# Sheet_2.net
KiCad netlist of a schematic drawn in Altium Designer
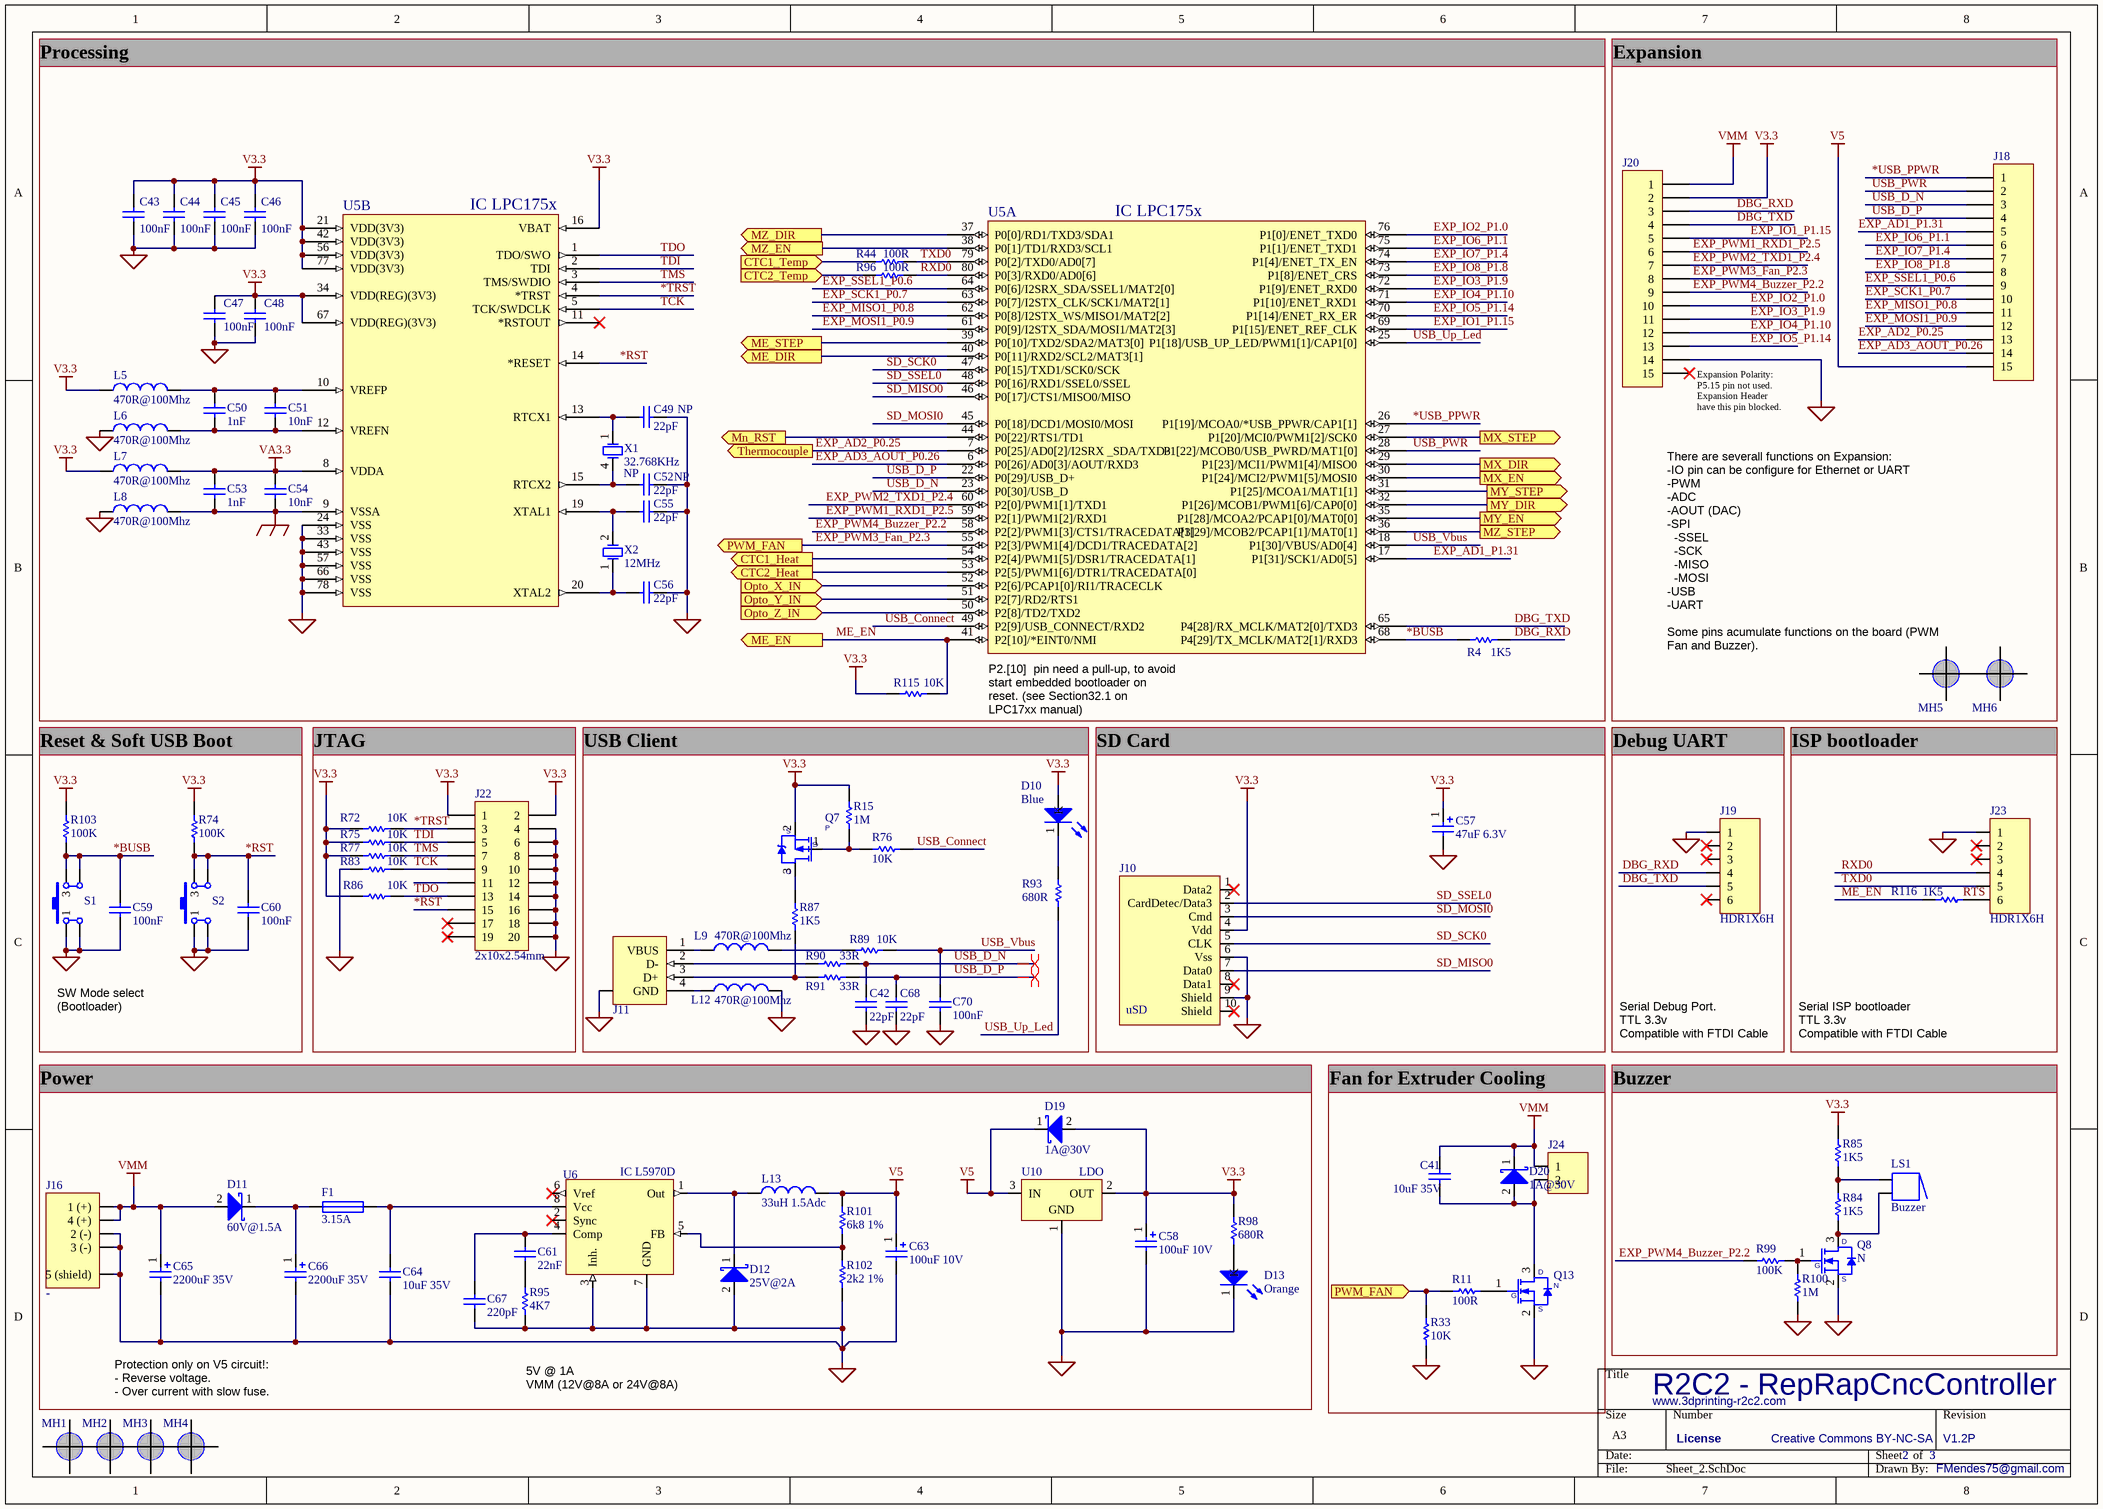
[diagram p0: Sheet_2.SchDoc]

(export (version "E")
  (design (tool "Eeschema 10.0.6"))
  (components
    (comp (ref "C41")
      (value "10uF 35V")
      (footprint "CAPC3216M")
      (description "Capacitor - MLCC; 10uF; 35V;")
      (fields (field (name "PART NUMBER") "10000002") (field (name "MANUFACTURER") "Taiyo Yuden"))
      (libsource (lib "HB_DB_Components") (part "Cap Non Pol"))
    )
    (comp (ref "C42")
      (value "22pF")
      (footprint "CAPC1608M")
      (description "Capacitor - MLCC; 0603; NP0; 50V")
      (fields (field (name "PART NUMBER") "10000056") (field (name "MANUFACTURER") "Multicomp"))
      (libsource (lib "HB_DB_Components") (part "Cap Non Pol"))
    )
    (comp (ref "C43")
      (value "100nF")
      (footprint "CAPC1608M")
      (description "Capacitor - MLCC; 0603; NP0; 50V")
      (fields (field (name "PART NUMBER") "10000054") (field (name "MANUFACTURER") "Multicomp"))
      (libsource (lib "HB_DB_Components") (part "Cap Non Pol"))
    )
    (comp (ref "C44")
      (value "100nF")
      (footprint "CAPC1608M")
      (description "Capacitor - MLCC; 0603; NP0; 50V")
      (fields (field (name "PART NUMBER") "10000054") (field (name "MANUFACTURER") "Multicomp"))
      (libsource (lib "HB_DB_Components") (part "Cap Non Pol"))
    )
    (comp (ref "C45")
      (value "100nF")
      (footprint "CAPC1608M")
      (description "Capacitor - MLCC; 0603; NP0; 50V")
      (fields (field (name "PART NUMBER") "10000054") (field (name "MANUFACTURER") "Multicomp"))
      (libsource (lib "HB_DB_Components") (part "Cap Non Pol"))
    )
    (comp (ref "C46")
      (value "100nF")
      (footprint "CAPC1608M")
      (description "Capacitor - MLCC; 0603; NP0; 50V")
      (fields (field (name "PART NUMBER") "10000054") (field (name "MANUFACTURER") "Multicomp"))
      (libsource (lib "HB_DB_Components") (part "Cap Non Pol"))
    )
    (comp (ref "C47")
      (value "100nF")
      (footprint "CAPC1608M")
      (description "Capacitor - MLCC; 0603; NP0; 50V")
      (fields (field (name "PART NUMBER") "10000054") (field (name "MANUFACTURER") "Multicomp"))
      (libsource (lib "HB_DB_Components") (part "Cap Non Pol"))
    )
    (comp (ref "C48")
      (value "100nF")
      (footprint "CAPC1608M")
      (description "Capacitor - MLCC; 0603; NP0; 50V")
      (fields (field (name "PART NUMBER") "10000054") (field (name "MANUFACTURER") "Multicomp"))
      (libsource (lib "HB_DB_Components") (part "Cap Non Pol"))
    )
    (comp (ref "C49")
      (value "22pF")
      (footprint "CAPC1608M")
      (description "Capacitor - MLCC; 0603; NP0; 50V")
      (fields
        (field (name "PART NUMBER") "10000056")
        (field (name "MANUFACTURER") "Multicomp")
        (field (name "POPULATE") "NP")
      )
      (libsource (lib "HB_DB_Components") (part "Cap Non Pol"))
    )
    (comp (ref "C50")
      (value "1nF")
      (footprint "CAPC1608M")
      (description "Capacitor - MLCC; 0603; NP0; 50V")
      (fields (field (name "PART NUMBER") "10000058") (field (name "MANUFACTURER") "Multicomp"))
      (libsource (lib "HB_DB_Components") (part "Cap Non Pol"))
    )
    (comp (ref "C51")
      (value "10nF")
      (footprint "CAPC1608M")
      (description "Capacitor - MLCC; 0603; NP0; 50V")
      (fields (field (name "PART NUMBER") "10000057") (field (name "MANUFACTURER") "Multicomp"))
      (libsource (lib "HB_DB_Components") (part "Cap Non Pol"))
    )
    (comp (ref "C52")
      (value "22pF")
      (footprint "CAPC1608M")
      (description "Capacitor - MLCC; 0603; NP0; 50V")
      (fields
        (field (name "PART NUMBER") "10000056")
        (field (name "MANUFACTURER") "Multicomp")
        (field (name "POPULATE") "NP")
      )
      (libsource (lib "HB_DB_Components") (part "Cap Non Pol"))
    )
    (comp (ref "C53")
      (value "1nF")
      (footprint "CAPC1608M")
      (description "Capacitor - MLCC; 0603; NP0; 50V")
      (fields (field (name "PART NUMBER") "10000058") (field (name "MANUFACTURER") "Multicomp"))
      (libsource (lib "HB_DB_Components") (part "Cap Non Pol"))
    )
    (comp (ref "C54")
      (value "10nF")
      (footprint "CAPC1608M")
      (description "Capacitor - MLCC; 0603; NP0; 50V")
      (fields (field (name "PART NUMBER") "10000057") (field (name "MANUFACTURER") "Multicomp"))
      (libsource (lib "HB_DB_Components") (part "Cap Non Pol"))
    )
    (comp (ref "C55")
      (value "22pF")
      (footprint "CAPC1608M")
      (description "Capacitor - MLCC; 0603; NP0; 50V")
      (fields (field (name "PART NUMBER") "10000056") (field (name "MANUFACTURER") "Multicomp"))
      (libsource (lib "HB_DB_Components") (part "Cap Non Pol"))
    )
    (comp (ref "C56")
      (value "22pF")
      (footprint "CAPC1608M")
      (description "Capacitor - MLCC; 0603; NP0; 50V")
      (fields (field (name "PART NUMBER") "10000056") (field (name "MANUFACTURER") "Multicomp"))
      (libsource (lib "HB_DB_Components") (part "Cap Non Pol"))
    )
    (comp (ref "C57")
      (value "47uF 6.3V")
      (footprint "CAPCP3825M")
      (description "Capacitor - MLCC Y5V; 47UF; 6.3V")
      (fields (field (name "PART NUMBER") "10000005") (field (name "MANUFACTURER") "MULTICOMP"))
      (libsource (lib "HB_DB_Components") (part "Cap Pol"))
    )
    (comp (ref "C58")
      (value "100uF 10V")
      (footprint "CAPAE6666X54M")
      (description "Capacitor - Al. Electrolytic; 100uF, 16V")
      (fields (field (name "PART NUMBER") "10000086") (field (name "MANUFACTURER") "Nichicon"))
      (libsource (lib "HB_DB_Components") (part "Cap Pol"))
    )
    (comp (ref "C59")
      (value "100nF")
      (footprint "CAPC1608M")
      (description "Capacitor - MLCC; 0603; NP0; 50V")
      (fields (field (name "PART NUMBER") "10000054") (field (name "MANUFACTURER") "Multicomp"))
      (libsource (lib "HB_DB_Components") (part "Cap Non Pol"))
    )
    (comp (ref "C60")
      (value "100nF")
      (footprint "CAPC1608M")
      (description "Capacitor - MLCC; 0603; NP0; 50V")
      (fields (field (name "PART NUMBER") "10000054") (field (name "MANUFACTURER") "Multicomp"))
      (libsource (lib "HB_DB_Components") (part "Cap Non Pol"))
    )
    (comp (ref "C61")
      (value "22nF")
      (footprint "CAPC1608M")
      (description "Capacitor - MLCC; 0603; NP0; 50V")
      (fields (field (name "PART NUMBER") "10000066") (field (name "MANUFACTURER") "Multicomp"))
      (libsource (lib "HB_DB_Components") (part "Cap Non Pol"))
    )
    (comp (ref "C63")
      (value "100uF 10V")
      (footprint "CAPAE6666X54M")
      (description "Capacitor - Al. Electrolytic; 100uF, 16V")
      (fields (field (name "PART NUMBER") "10000086") (field (name "MANUFACTURER") "Nichicon"))
      (libsource (lib "HB_DB_Components") (part "Cap Pol"))
    )
    (comp (ref "C64")
      (value "10uF 35V")
      (footprint "CAPC3216M")
      (description "Capacitor - MLCC; 10uF; 35V;")
      (fields (field (name "PART NUMBER") "10000002") (field (name "MANUFACTURER") "Taiyo Yuden"))
      (libsource (lib "HB_DB_Components") (part "Cap Non Pol"))
    )
    (comp (ref "C65")
      (value "2200uF 35V")
      (footprint "CAPPR7.5-16x25")
      (description "Capacitor - Al. Electrolytic; 2200uF; 35V")
      (fields (field (name "PART NUMBER") "10000006") (field (name "MANUFACTURER") "PANASONIC"))
      (libsource (lib "HB_DB_Components") (part "Cap Pol"))
    )
    (comp (ref "C66")
      (value "2200uF 35V")
      (footprint "CAPPR7.5-16x25")
      (description "Capacitor - Al. Electrolytic; 2200uF; 35V")
      (fields (field (name "PART NUMBER") "10000006") (field (name "MANUFACTURER") "PANASONIC"))
      (libsource (lib "HB_DB_Components") (part "Cap Pol"))
    )
    (comp (ref "C67")
      (value "220pF")
      (footprint "CAPC1608M")
      (description "Capacitor - MLCC; 0603; NP0; 50V")
      (fields (field (name "PART NUMBER") "10000055") (field (name "MANUFACTURER") "Multicomp"))
      (libsource (lib "HB_DB_Components") (part "Cap Non Pol"))
    )
    (comp (ref "C68")
      (value "22pF")
      (footprint "CAPC1608M")
      (description "Capacitor - MLCC; 0603; NP0; 50V")
      (fields (field (name "PART NUMBER") "10000056") (field (name "MANUFACTURER") "Multicomp"))
      (libsource (lib "HB_DB_Components") (part "Cap Non Pol"))
    )
    (comp (ref "C70")
      (value "100nF")
      (footprint "CAPC1608M")
      (description "Capacitor - MLCC; 0603; NP0; 50V")
      (fields (field (name "PART NUMBER") "10000054") (field (name "MANUFACTURER") "Multicomp"))
      (libsource (lib "HB_DB_Components") (part "Cap Non Pol"))
    )
    (comp (ref "D10")
      (value "Blue")
      (footprint "LEDM_3216X12M")
      (description "Led - 1206; Blue OSRAM")
      (fields (field (name "PART NUMBER") "10000065") (field (name "MANUFACTURER") "OSRAM"))
      (libsource (lib "HB_DB_Components") (part "LED"))
    )
    (comp (ref "D11")
      (value "60V@1.5A")
      (footprint "SMA")
      (description "Diode - Schottky; 1.5A; 60V")
      (fields (field (name "PART NUMBER") "10000010") (field (name "MANUFACTURER") "VISHAY"))
      (libsource (lib "HB_DB_Components") (part "D Schottky"))
    )
    (comp (ref "D12")
      (value "25V@2A")
      (footprint "SMB")
      (description "Diode - Schottky; 25V; 2A")
      (fields (field (name "PART NUMBER") "10000009") (field (name "MANUFACTURER") "ST"))
      (libsource (lib "HB_DB_Components") (part "D Schottky"))
    )
    (comp (ref "D13")
      (value "Orange")
      (footprint "LEDM_3216X12M")
      (description "Led - 1206; Orange OSRAM")
      (fields (field (name "PART NUMBER") "10000007") (field (name "MANUFACTURER") "OSRAM"))
      (libsource (lib "HB_DB_Components") (part "LED"))
    )
    (comp (ref "D19")
      (value "1A@30V")
      (footprint "SOD323")
      (description "Diode - Schottky; 30V; 1A;")
      (fields (field (name "PART NUMBER") "10000085") (field (name "MANUFACTURER") "NXP"))
      (libsource (lib "HB_DB_Components") (part "D Schottky"))
    )
    (comp (ref "D20")
      (value "1A@30V")
      (footprint "SOD323")
      (description "Diode - Schottky; 30V; 1A;")
      (fields (field (name "PART NUMBER") "10000085") (field (name "MANUFACTURER") "NXP"))
      (libsource (lib "HB_DB_Components") (part "D Schottky"))
    )
    (comp (ref "F1")
      (value "3.15A")
      (footprint "RESC1608M")
      (description "Fuse - 0603; Itrip=3.15A")
      (fields (field (name "PART NUMBER") "10000011") (field (name "MANUFACTURER") "Bourns"))
      (libsource (lib "HB_DB_Components") (part "F"))
    )
    (comp (ref "J10")
      (value "uSD")
      (footprint "3M_2900")
      (description "Connector - MicroSD Card 8pin; PCB; Gold")
      (fields (field (name "PART NUMBER") "10000029") (field (name "MANUFACTURER") "Amphenol"))
      (libsource (lib "HB_DB_Components") (part "Con uSD"))
    )
    (comp (ref "J11") (value "Con 4 USB") (libsource (lib "HB") (part "Con 4 USB")))
    (comp (ref "J16")
      (value "-")
      (footprint "KYCON_KPJX-4S")
      (description "Connector - PCB; Female Receptacle; 4 way; Hor.")
      (fields (field (name "PART NUMBER") "10000099") (field (name "MANUFACTURER") "Kycon"))
      (libsource (lib "HB_DB_Components") (part "Con 5 KPJX-4S"))
    )
    (comp (ref "J18")
      (value "Con 15")
      (footprint "HDR1X15")
      (description "Connector - Header 15x1")
      (fields (field (name "PART NUMBER") "10000067"))
      (libsource (lib "HB_DB_Components") (part "Con 15"))
    )
    (comp (ref "J19")
      (value "HDR1X6H")
      (footprint "HDR1X6H")
      (description "Connector - Header 1x6; Hor.")
      (fields (field (name "PART NUMBER") "10000074"))
      (libsource (lib "HB_DB_Components") (part "Con 6"))
    )
    (comp (ref "J20")
      (value "Con 15")
      (footprint "HDR1X15")
      (description "Connector - Header 15x1")
      (fields (field (name "PART NUMBER") "10000067"))
      (libsource (lib "") (part "Con 15_1"))
    )
    (comp (ref "J22")
      (value "2x10x2.54mm")
      (footprint "HDR2X10")
      (description "Connector - PCB; Male Receptacle; 2.54mm; 2way; Vert.")
      (fields (field (name "PART NUMBER") "10000064") (field (name "MANUFACTURER") "SAMTEC"))
      (libsource (lib "HB_DB_Components") (part "Con 10X2"))
    )
    (comp (ref "J23")
      (value "HDR1X6H")
      (footprint "HDR1X6H")
      (description "Connector - Header 1x6; Hor.")
      (fields (field (name "PART NUMBER") "10000074"))
      (libsource (lib "HB_DB_Components") (part "Con 6"))
    )
    (comp (ref "J24")
      (value "Con 2")
      (footprint "MOLEX_22-29-2021")
      (description "Connector - PCB; Header; SQ Pin, 2 way; 2.54mm; Vert")
      (fields (field (name "PART NUMBER") "10000097") (field (name "MANUFACTURER") "Molex"))
      (libsource (lib "HB_DB_Components") (part "Con 2"))
    )
    (comp (ref "L5")
      (value "470R@100Mhz")
      (footprint "INDC1608M")
      (description "Ferrite Bead - 470OHM; 0603")
      (fields (field (name "PART NUMBER") "10000032") (field (name "MANUFACTURER") "MURATA"))
      (libsource (lib "HB_DB_Components") (part "Ind"))
    )
    (comp (ref "L6")
      (value "470R@100Mhz")
      (footprint "INDC1608M")
      (description "Ferrite Bead - 470OHM; 0603")
      (fields (field (name "PART NUMBER") "10000032") (field (name "MANUFACTURER") "MURATA"))
      (libsource (lib "HB_DB_Components") (part "Ind"))
    )
    (comp (ref "L7")
      (value "470R@100Mhz")
      (footprint "INDC1608M")
      (description "Ferrite Bead - 470OHM; 0603")
      (fields (field (name "PART NUMBER") "10000032") (field (name "MANUFACTURER") "MURATA"))
      (libsource (lib "HB_DB_Components") (part "Ind"))
    )
    (comp (ref "L8")
      (value "470R@100Mhz")
      (footprint "INDC1608M")
      (description "Ferrite Bead - 470OHM; 0603")
      (fields (field (name "PART NUMBER") "10000032") (field (name "MANUFACTURER") "MURATA"))
      (libsource (lib "HB_DB_Components") (part "Ind"))
    )
    (comp (ref "L9")
      (value "470R@100Mhz")
      (footprint "INDC1608M")
      (description "Ferrite Bead - 470OHM; 0603")
      (fields (field (name "PART NUMBER") "10000032") (field (name "MANUFACTURER") "MURATA"))
      (libsource (lib "HB_DB_Components") (part "Ind"))
    )
    (comp (ref "L12")
      (value "470R@100Mhz")
      (footprint "INDC1608M")
      (description "Ferrite Bead - 470OHM; 0603")
      (fields (field (name "PART NUMBER") "10000032") (field (name "MANUFACTURER") "MURATA"))
      (libsource (lib "HB_DB_Components") (part "Ind"))
    )
    (comp (ref "L13")
      (value "33uH 1.5Adc")
      (footprint "INDP9898X58M")
      (description "Inductor - 33uH; Isat=2.9A; In=1.5A")
      (fields (field (name "PART NUMBER") "10000081") (field (name "MANUFACTURER") "Bourns"))
      (libsource (lib "HB_DB_Components") (part "Ind"))
    )
    (comp (ref "LS1")
      (value "Buzzer")
      (footprint "TDK_PS17")
      (description "Buzzer - Piezo; 70dB; Diam.17mm")
      (fields (field (name "PART NUMBER") "10000068") (field (name "MANUFACTURER") "TDK"))
      (libsource (lib "HB_DB_Components") (part "Buzzer"))
    )
    (comp (ref "MH1")
      (value "MH")
      (footprint "MH_M3")
      (description "PCB Symbol - Mounting Hole M3")
      (fields (field (name "PART NUMBER") "1000000"))
      (libsource (lib "HB_DB_Components") (part "MH"))
    )
    (comp (ref "MH2")
      (value "MH")
      (footprint "MH_M3")
      (description "PCB Symbol - Mounting Hole M3")
      (fields (field (name "PART NUMBER") "1000000"))
      (libsource (lib "HB_DB_Components") (part "MH"))
    )
    (comp (ref "MH3")
      (value "MH")
      (footprint "MH_M3")
      (description "PCB Symbol - Mounting Hole M3")
      (fields (field (name "PART NUMBER") "1000000"))
      (libsource (lib "HB_DB_Components") (part "MH"))
    )
    (comp (ref "MH4")
      (value "MH")
      (footprint "MH_M3")
      (description "PCB Symbol - Mounting Hole M3")
      (fields (field (name "PART NUMBER") "1000000"))
      (libsource (lib "HB_DB_Components") (part "MH"))
    )
    (comp (ref "MH5")
      (value "MH")
      (footprint "MH_M3_2")
      (description "PCB Symbol - Mounting Hole M3")
      (fields (field (name "PART NUMBER") "100001"))
      (libsource (lib "HB_DB_Components") (part "MH"))
    )
    (comp (ref "MH6")
      (value "MH")
      (footprint "MH_M3_2")
      (description "PCB Symbol - Mounting Hole M3")
      (fields (field (name "PART NUMBER") "100001"))
      (libsource (lib "HB_DB_Components") (part "MH"))
    )
    (comp (ref "Q7")
      (value "P")
      (footprint "SOT23-3M")
      (description "Mosfet - Power; Vdss=-30v; Rds=0.60; Id=-0.6A")
      (fields (field (name "PART NUMBER") "10000076") (field (name "MANUFACTURER") "IR"))
      (libsource (lib "HB_DB_Components") (part "MOS-P"))
    )
    (comp (ref "Q8")
      (value "N")
      (footprint "SOT323-3AM")
      (description "Mosfet - N; 60V; 0.3A;")
      (fields (field (name "PART NUMBER") "10000039") (field (name "MANUFACTURER") "NXP"))
      (libsource (lib "HB_DB_Components") (part "Q MOSFET-N"))
    )
    (comp (ref "Q13")
      (value "N")
      (footprint "SOT323-3AM")
      (description "Mosfet - N; 60V; 0.3A;")
      (fields (field (name "PART NUMBER") "10000039") (field (name "MANUFACTURER") "NXP"))
      (libsource (lib "HB_DB_Components") (part "Q MOSFET-N"))
    )
    (comp (ref "R4")
      (value "1K5")
      (footprint "RESC1608M")
      (description "Resistor")
      (fields (field (name "PART NUMBER") "10000048") (field (name "MANUFACTURER") "Multicomp"))
      (libsource (lib "HB_DB_Components") (part "Res"))
    )
    (comp (ref "R11")
      (value "100R")
      (footprint "RESC1608M")
      (description "Resistor - 0603; 0.063W; 1%")
      (fields (field (name "PART NUMBER") "10000042") (field (name "MANUFACTURER") "Multicomp"))
      (libsource (lib "HB_DB_Components") (part "Res"))
    )
    (comp (ref "R15")
      (value "1M")
      (footprint "RESC1608M")
      (description "Resistor - 0603; 0.063W; 1%")
      (fields (field (name "PART NUMBER") "10000049") (field (name "MANUFACTURER") "Multicomp"))
      (libsource (lib "HB_DB_Components") (part "Res"))
    )
    (comp (ref "R33")
      (value "10K")
      (footprint "RESC1608M")
      (description "Resistor - 0603; 0.063W; 1%")
      (fields (field (name "PART NUMBER") "10000044") (field (name "MANUFACTURER") "Multicomp"))
      (libsource (lib "HB_DB_Components") (part "Res"))
    )
    (comp (ref "R44")
      (value "100R")
      (footprint "RESC1608M")
      (description "Resistor - 0603; 0.063W; 1%")
      (fields (field (name "PART NUMBER") "10000042") (field (name "MANUFACTURER") "Multicomp"))
      (libsource (lib "HB_DB_Components") (part "Res"))
    )
    (comp (ref "R72")
      (value "10K")
      (footprint "RESC1608M")
      (description "Resistor - 0603; 0.063W; 1%")
      (fields (field (name "PART NUMBER") "10000044") (field (name "MANUFACTURER") "Multicomp"))
      (libsource (lib "HB_DB_Components") (part "Res"))
    )
    (comp (ref "R74")
      (value "100K")
      (footprint "RESC1608M")
      (description "Resistor - 0603; 0.063W; 1%")
      (fields (field (name "PART NUMBER") "10000045") (field (name "MANUFACTURER") "Multicomp"))
      (libsource (lib "HB_DB_Components") (part "Res"))
    )
    (comp (ref "R75")
      (value "10K")
      (footprint "RESC1608M")
      (description "Resistor - 0603; 0.063W; 1%")
      (fields (field (name "PART NUMBER") "10000044") (field (name "MANUFACTURER") "Multicomp"))
      (libsource (lib "HB_DB_Components") (part "Res"))
    )
    (comp (ref "R76")
      (value "10K")
      (footprint "RESC1608M")
      (description "Resistor - 0603; 0.063W; 1%")
      (fields (field (name "PART NUMBER") "10000044") (field (name "MANUFACTURER") "Multicomp"))
      (libsource (lib "HB_DB_Components") (part "Res"))
    )
    (comp (ref "R77")
      (value "10K")
      (footprint "RESC1608M")
      (description "Resistor - 0603; 0.063W; 1%")
      (fields (field (name "PART NUMBER") "10000044") (field (name "MANUFACTURER") "Multicomp"))
      (libsource (lib "HB_DB_Components") (part "Res"))
    )
    (comp (ref "R83")
      (value "10K")
      (footprint "RESC1608M")
      (description "Resistor - 0603; 0.063W; 1%")
      (fields (field (name "PART NUMBER") "10000044") (field (name "MANUFACTURER") "Multicomp"))
      (libsource (lib "HB_DB_Components") (part "Res"))
    )
    (comp (ref "R84")
      (value "1K5")
      (footprint "RESC1608M")
      (description "Resistor - 0603; 0.063W; 1%")
      (fields (field (name "PART NUMBER") "10000048") (field (name "MANUFACTURER") "Multicomp"))
      (libsource (lib "HB_DB_Components") (part "Res"))
    )
    (comp (ref "R85")
      (value "1K5")
      (footprint "RESC1608M")
      (description "Resistor - 0603; 0.063W; 1%")
      (fields (field (name "PART NUMBER") "10000048") (field (name "MANUFACTURER") "Multicomp"))
      (libsource (lib "HB_DB_Components") (part "Res"))
    )
    (comp (ref "R86")
      (value "10K")
      (footprint "RESC1608M")
      (description "Resistor - 0603; 0.063W; 1%")
      (fields (field (name "PART NUMBER") "10000044") (field (name "MANUFACTURER") "Multicomp"))
      (libsource (lib "HB_DB_Components") (part "Res"))
    )
    (comp (ref "R87")
      (value "1K5")
      (footprint "RESC1608M")
      (description "Resistor - 0603; 0.063W; 1%")
      (fields (field (name "PART NUMBER") "10000048") (field (name "MANUFACTURER") "Multicomp"))
      (libsource (lib "HB_DB_Components") (part "Res"))
    )
    (comp (ref "R89")
      (value "10K")
      (footprint "RESC1608M")
      (description "Resistor - 0603; 0.063W; 1%")
      (fields (field (name "PART NUMBER") "10000044") (field (name "MANUFACTURER") "Multicomp"))
      (libsource (lib "HB_DB_Components") (part "Res"))
    )
    (comp (ref "R90")
      (value "33R")
      (footprint "RESC1608M")
      (description "Resistor - 0603; 0.063W; 1%")
      (fields (field (name "PART NUMBER") "10000053") (field (name "MANUFACTURER") "Multicomp"))
      (libsource (lib "HB_DB_Components") (part "Res"))
    )
    (comp (ref "R91")
      (value "33R")
      (footprint "RESC1608M")
      (description "Resistor - 0603; 0.063W; 1%")
      (fields (field (name "PART NUMBER") "10000053") (field (name "MANUFACTURER") "Multicomp"))
      (libsource (lib "HB_DB_Components") (part "Res"))
    )
    (comp (ref "R93")
      (value "680R")
      (footprint "RESC1608M")
      (description "Resistor - 0603; 0.063W; 1%")
      (fields (field (name "PART NUMBER") "10000061") (field (name "MANUFACTURER") "Multicomp"))
      (libsource (lib "HB_DB_Components") (part "Res"))
    )
    (comp (ref "R95")
      (value "4K7")
      (footprint "RESC1608M")
      (description "Resistor - 0603; 0.063W; 1%")
      (fields (field (name "PART NUMBER") "10000050") (field (name "MANUFACTURER") "Multicomp"))
      (libsource (lib "HB_DB_Components") (part "Res"))
    )
    (comp (ref "R96")
      (value "100R")
      (footprint "RESC1608M")
      (description "Resistor - 0603; 0.063W; 1%")
      (fields (field (name "PART NUMBER") "10000042") (field (name "MANUFACTURER") "Multicomp"))
      (libsource (lib "HB_DB_Components") (part "Res"))
    )
    (comp (ref "R98")
      (value "680R")
      (footprint "RESC1608M")
      (description "Resistor - 0603; 0.063W; 1%")
      (fields (field (name "PART NUMBER") "10000061") (field (name "MANUFACTURER") "Multicomp"))
      (libsource (lib "HB_DB_Components") (part "Res"))
    )
    (comp (ref "R99")
      (value "100K")
      (footprint "RESC1608M")
      (description "Resistor - 0603; 0.063W; 1%")
      (fields (field (name "PART NUMBER") "10000045") (field (name "MANUFACTURER") "Multicomp"))
      (libsource (lib "HB_DB_Components") (part "Res"))
    )
    (comp (ref "R100")
      (value "1M")
      (footprint "RESC1608M")
      (description "Resistor - 0603; 0.063W; 1%")
      (fields (field (name "PART NUMBER") "10000049") (field (name "MANUFACTURER") "Multicomp"))
      (libsource (lib "HB_DB_Components") (part "Res"))
    )
    (comp (ref "R101")
      (value "6k8 1%")
      (footprint "RESC1608M")
      (description "Resistor - 0603; 0.063W; 1%")
      (fields (field (name "PART NUMBER") "10000080") (field (name "MANUFACTURER") "Vishay"))
      (libsource (lib "HB_DB_Components") (part "Res"))
    )
    (comp (ref "R102")
      (value "2k2 1%")
      (footprint "RESC1608M")
      (description "Resistor - 0603; 0.063W; 1%")
      (fields (field (name "PART NUMBER") "10000079") (field (name "MANUFACTURER") "Vishay"))
      (libsource (lib "HB_DB_Components") (part "Res"))
    )
    (comp (ref "R103")
      (value "100K")
      (footprint "RESC1608M")
      (description "Resistor - 0603; 0.063W; 1%")
      (fields (field (name "PART NUMBER") "10000045") (field (name "MANUFACTURER") "Multicomp"))
      (libsource (lib "HB_DB_Components") (part "Res"))
    )
    (comp (ref "R115")
      (value "10K")
      (footprint "RESC1608M")
      (description "Resistor - 0603; 0.063W; 1%")
      (fields (field (name "PART NUMBER") "10000044") (field (name "MANUFACTURER") "Multicomp"))
      (libsource (lib "HB_DB_Components") (part "Res"))
    )
    (comp (ref "R116")
      (value "1K5")
      (footprint "RESC1608M")
      (description "Resistor - 0603; 0.063W; 1%")
      (fields (field (name "PART NUMBER") "10000048") (field (name "MANUFACTURER") "Multicomp"))
      (libsource (lib "HB_DB_Components") (part "Res"))
    )
    (comp (ref "S1")
      (value "SW-PB")
      (footprint "SW_FSM6JSMA")
      (description "Switch - Micro; Tactile; SPNO")
      (fields (field (name "PART NUMBER") "10000019") (field (name "MANUFACTURER") "TYCO"))
      (libsource (lib "HB_DB_Components") (part "SW-PB"))
    )
    (comp (ref "S2")
      (value "SW-PB")
      (footprint "SW_FSM6JSMA")
      (description "Switch - Micro; Tactile; SPNO")
      (fields (field (name "PART NUMBER") "10000019") (field (name "MANUFACTURER") "TYCO"))
      (libsource (lib "HB_DB_Components") (part "SW-PB"))
    )
    (comp (ref "U5")
      (value "IC LPC175x")
      (footprint "TSQFP50P1400X1400X160-80M")
      (description "IC - uController ARM Cortex-M3, 100MHz")
      (fields (field (name "PART NUMBER") "10000013") (field (name "MANUFACTURER") "NXP"))
      (libsource (lib "HB_DB_Components") (part "IC LPC175x"))
    )
    (comp (ref "U6")
      (value "IC L5970D")
      (footprint "SOIC127P600-8M")
      (description "IC - DC-DC Reg.")
      (fields (field (name "PART NUMBER") "10000017") (field (name "MANUFACTURER") "ST"))
      (libsource (lib "HB_DB_Components") (part "IC L5970D"))
    )
    (comp (ref "U10")
      (value "LDO")
      (footprint "SOT223-4M")
      (description "IC - Fixed LDO Voltage Reg 3.3V 800mA")
      (fields (field (name "PART NUMBER") "10000082") (field (name "MANUFACTURER") "TI"))
      (libsource (lib "HB_DB_Components") (part "IC_TLV1117-3.3"))
    )
    (comp (ref "X1")
      (value "32.768KHz")
      (footprint "XTAL_800P380X250-4M")
      (description "Crystal - 32.768 kHz Low Profile; PLastic")
      (fields
        (field (name "PART NUMBER") "10000063")
        (field (name "MANUFACTURER") "ABRACON")
        (field (name "POPULATE") "NP")
      )
      (libsource (lib "HB_DB_Components") (part "XTAL_4"))
    )
    (comp (ref "X2")
      (value "12MHz")
      (footprint "HC49/4H_SMX")
      (description "Crystal - 12.0MHz")
      (fields (field (name "PART NUMBER") "10000040"))
      (libsource (lib "HB_DB_Components") (part "XTAL"))
    )
  )
  (nets
    (net (code "1") (name "/*BUSB") (class "Default")
      (node (ref "C59") (pin "2") (pinfunction "2_2") (pintype "passive"))
      (node (ref "R103") (pin "1") (pinfunction "1_1") (pintype "passive"))
      (node (ref "R4") (pin "1") (pinfunction "1_1") (pintype "passive"))
      (node (ref "S1") (pin "3") (pinfunction "3_3") (pintype "passive"))
      (node (ref "S1") (pin "4") (pinfunction "4_4") (pintype "passive"))
      (node (ref "U5") (pin "68") (pinfunction "P4[29]/TX_MCLK/MAT2[1]/RXD3_68") (pintype "bidirectional"))
    )
    (net (code "2") (name "/*RST") (class "Default")
      (node (ref "C60") (pin "2") (pinfunction "2_2") (pintype "passive"))
      (node (ref "J22") (pin "15") (pinfunction "15_15") (pintype "passive"))
      (node (ref "R74") (pin "1") (pinfunction "1_1") (pintype "passive"))
      (node (ref "S2") (pin "3") (pinfunction "3_3") (pintype "passive"))
      (node (ref "S2") (pin "4") (pinfunction "4_4") (pintype "passive"))
      (node (ref "U5") (pin "14") (pinfunction "*RESET_14") (pintype "input"))
    )
    (net (code "3") (name "/*TRST") (class "Default")
      (node (ref "J22") (pin "3") (pinfunction "3_3") (pintype "passive"))
      (node (ref "R72") (pin "2") (pinfunction "2_2") (pintype "passive"))
      (node (ref "U5") (pin "4") (pinfunction "*TRST_4") (pintype "input"))
    )
    (net (code "4") (name "/*USB_PPWR") (class "Default")
      (node (ref "J18") (pin "1") (pinfunction "1_1") (pintype "passive"))
      (node (ref "U5") (pin "26") (pinfunction "P1[19]/MCOA0/*USB_PPWR/CAP1[1]_26") (pintype "bidirectional"))
    )
    (net (code "5") (name "/CTC1_Heat") (class "Default")
      (node (ref "U5") (pin "54") (pinfunction "P2[4]/PWM1[5]/DSR1/TRACEDATA[1]_54") (pintype "bidirectional"))
    )
    (net (code "6") (name "/CTC1_Temp") (class "Default")
      (node (ref "R44") (pin "1") (pinfunction "1_1") (pintype "passive"))
    )
    (net (code "7") (name "/CTC2_Heat") (class "Default")
      (node (ref "U5") (pin "53") (pinfunction "P2[5]/PWM1[6]/DTR1/TRACEDATA[0]_53") (pintype "bidirectional"))
    )
    (net (code "8") (name "/CTC2_Temp") (class "Default")
      (node (ref "R96") (pin "1") (pinfunction "1_1") (pintype "passive"))
    )
    (net (code "9") (name "/DBG_RXD") (class "Default")
      (node (ref "J19") (pin "4") (pinfunction "4_4") (pintype "passive"))
      (node (ref "J20") (pin "3") (pinfunction "3_3") (pintype "passive"))
      (node (ref "R4") (pin "2") (pinfunction "2_2") (pintype "passive"))
    )
    (net (code "10") (name "/DBG_TXD") (class "Default")
      (node (ref "J19") (pin "5") (pinfunction "5_5") (pintype "passive"))
      (node (ref "J20") (pin "4") (pinfunction "4_4") (pintype "passive"))
      (node (ref "U5") (pin "65") (pinfunction "P4[28]/RX_MCLK/MAT2[0]/TXD3_65") (pintype "bidirectional"))
    )
    (net (code "11") (name "/EXP_AD1_P1.31") (class "Default")
      (node (ref "J18") (pin "5") (pinfunction "5_5") (pintype "passive"))
      (node (ref "U5") (pin "17") (pinfunction "P1[31]/SCK1/AD0[5]_17") (pintype "bidirectional"))
    )
    (net (code "12") (name "/EXP_AD2_P0.25") (class "Default")
      (node (ref "J18") (pin "13") (pinfunction "13_13") (pintype "passive"))
      (node (ref "U5") (pin "7") (pinfunction "P0[25]/AD0[2]/I2SRX__SDA/TXD3_7") (pintype "bidirectional"))
    )
    (net (code "13") (name "/EXP_AD3_AOUT_P0.26") (class "Default")
      (node (ref "J18") (pin "14") (pinfunction "14_14") (pintype "passive"))
      (node (ref "U5") (pin "6") (pinfunction "P0[26]/AD0[3]/AOUT/RXD3_6") (pintype "bidirectional"))
    )
    (net (code "14") (name "/EXP_IO1_P1.15") (class "Default")
      (node (ref "J20") (pin "5") (pinfunction "5_5") (pintype "passive"))
      (node (ref "U5") (pin "69") (pinfunction "P1[15]/ENET_REF_CLK_69") (pintype "bidirectional"))
    )
    (net (code "15") (name "/EXP_IO2_P1.0") (class "Default")
      (node (ref "J20") (pin "10") (pinfunction "10_10") (pintype "passive"))
      (node (ref "U5") (pin "76") (pinfunction "P1[0]/ENET_TXD0_76") (pintype "bidirectional"))
    )
    (net (code "16") (name "/EXP_IO3_P1.9") (class "Default")
      (node (ref "J20") (pin "11") (pinfunction "11_11") (pintype "passive"))
      (node (ref "U5") (pin "72") (pinfunction "P1[9]/ENET_RXD0_72") (pintype "bidirectional"))
    )
    (net (code "17") (name "/EXP_IO4_P1.10") (class "Default")
      (node (ref "J20") (pin "12") (pinfunction "12_12") (pintype "passive"))
      (node (ref "U5") (pin "71") (pinfunction "P1[10]/ENET_RXD1_71") (pintype "bidirectional"))
    )
    (net (code "18") (name "/EXP_IO5_P1.14") (class "Default")
      (node (ref "J20") (pin "13") (pinfunction "13_13") (pintype "passive"))
      (node (ref "U5") (pin "70") (pinfunction "P1[14]/ENET_RX_ER_70") (pintype "bidirectional"))
    )
    (net (code "19") (name "/EXP_IO6_P1.1") (class "Default")
      (node (ref "J18") (pin "6") (pinfunction "6_6") (pintype "passive"))
      (node (ref "U5") (pin "75") (pinfunction "P1[1]/ENET_TXD1_75") (pintype "bidirectional"))
    )
    (net (code "20") (name "/EXP_IO7_P1.4") (class "Default")
      (node (ref "J18") (pin "7") (pinfunction "7_7") (pintype "passive"))
      (node (ref "U5") (pin "74") (pinfunction "P1[4]/ENET_TX_EN_74") (pintype "bidirectional"))
    )
    (net (code "21") (name "/EXP_IO8_P1.8") (class "Default")
      (node (ref "J18") (pin "8") (pinfunction "8_8") (pintype "passive"))
      (node (ref "U5") (pin "73") (pinfunction "P1[8]/ENET_CRS_73") (pintype "bidirectional"))
    )
    (net (code "22") (name "/EXP_MISO1_P0.8") (class "Default")
      (node (ref "J18") (pin "11") (pinfunction "11_11") (pintype "passive"))
      (node (ref "U5") (pin "62") (pinfunction "P0[8]/I2STX_WS/MISO1/MAT2[2]_62") (pintype "bidirectional"))
    )
    (net (code "23") (name "/EXP_MOSI1_P0.9") (class "Default")
      (node (ref "J18") (pin "12") (pinfunction "12_12") (pintype "passive"))
      (node (ref "U5") (pin "61") (pinfunction "P0[9]/I2STX_SDA/MOSI1/MAT2[3]_61") (pintype "bidirectional"))
    )
    (net (code "24") (name "/EXP_PWM1_RXD1_P2.5") (class "Default")
      (node (ref "J20") (pin "6") (pinfunction "6_6") (pintype "passive"))
      (node (ref "U5") (pin "59") (pinfunction "P2[1]/PWM1[2]/RXD1_59") (pintype "bidirectional"))
    )
    (net (code "25") (name "/EXP_PWM2_TXD1_P2.4") (class "Default")
      (node (ref "J20") (pin "7") (pinfunction "7_7") (pintype "passive"))
      (node (ref "U5") (pin "60") (pinfunction "P2[0]/PWM1[1]/TXD1_60") (pintype "bidirectional"))
    )
    (net (code "26") (name "/EXP_PWM3_Fan_P2.3") (class "Default")
      (node (ref "J20") (pin "8") (pinfunction "8_8") (pintype "passive"))
      (node (ref "R11") (pin "1") (pinfunction "1_1") (pintype "passive"))
      (node (ref "R33") (pin "2") (pinfunction "2_2") (pintype "passive"))
      (node (ref "U5") (pin "55") (pinfunction "P2[3]/PWM1[4]/DCD1/TRACEDATA[2]_55") (pintype "bidirectional"))
    )
    (net (code "27") (name "/EXP_PWM4_Buzzer_P2.2") (class "Default")
      (node (ref "J20") (pin "9") (pinfunction "9_9") (pintype "passive"))
      (node (ref "R99") (pin "1") (pinfunction "1_1") (pintype "passive"))
      (node (ref "U5") (pin "58") (pinfunction "P2[2]/PWM1[3]/CTS1/TRACEDATA[3]_58") (pintype "bidirectional"))
    )
    (net (code "28") (name "/EXP_SCK1_P0.7") (class "Default")
      (node (ref "J18") (pin "10") (pinfunction "10_10") (pintype "passive"))
      (node (ref "U5") (pin "63") (pinfunction "P0[7]/I2STX_CLK/SCK1/MAT2[1]_63") (pintype "bidirectional"))
    )
    (net (code "29") (name "/EXP_SSEL1_P0.6") (class "Default")
      (node (ref "J18") (pin "9") (pinfunction "9_9") (pintype "passive"))
      (node (ref "U5") (pin "64") (pinfunction "P0[6]/I2SRX_SDA/SSEL1/MAT2[0]_64") (pintype "bidirectional"))
    )
    (net (code "30") (name "/ME_DIR") (class "Default")
      (node (ref "U5") (pin "40") (pinfunction "P0[11]/RXD2/SCL2/MAT3[1]_40") (pintype "bidirectional"))
    )
    (net (code "31") (name "/ME_EN") (class "Default")
      (node (ref "R115") (pin "2") (pinfunction "2_2") (pintype "passive"))
      (node (ref "R116") (pin "1") (pinfunction "1_1") (pintype "passive"))
      (node (ref "U5") (pin "41") (pinfunction "P2[10]/*EINT0/NMI_41") (pintype "bidirectional"))
    )
    (net (code "32") (name "/ME_STEP") (class "Default")
      (node (ref "U5") (pin "39") (pinfunction "P0[10]/TXD2/SDA2/MAT3[0]_39") (pintype "bidirectional"))
    )
    (net (code "33") (name "/MX_DIR") (class "Default")
      (node (ref "U5") (pin "29") (pinfunction "P1[23]/MCI1/PWM1[4]/MISO0_29") (pintype "bidirectional"))
    )
    (net (code "34") (name "/MX_EN") (class "Default")
      (node (ref "U5") (pin "30") (pinfunction "P1[24]/MCI2/PWM1[5]/MOSI0_30") (pintype "bidirectional"))
    )
    (net (code "35") (name "/MX_STEP") (class "Default")
      (node (ref "U5") (pin "27") (pinfunction "P1[20]/MCI0/PWM1[2]/SCK0_27") (pintype "bidirectional"))
    )
    (net (code "36") (name "/MY_DIR") (class "Default")
      (node (ref "U5") (pin "32") (pinfunction "P1[26]/MCOB1/PWM1[6]/CAP0[0]_32") (pintype "bidirectional"))
    )
    (net (code "37") (name "/MY_EN") (class "Default")
      (node (ref "U5") (pin "35") (pinfunction "P1[28]/MCOA2/PCAP1[0]/MAT0[0]_35") (pintype "bidirectional"))
    )
    (net (code "38") (name "/MY_STEP") (class "Default")
      (node (ref "U5") (pin "31") (pinfunction "P1[25]/MCOA1/MAT1[1]_31") (pintype "bidirectional"))
    )
    (net (code "39") (name "/MZ_DIR") (class "Default")
      (node (ref "U5") (pin "37") (pinfunction "P0[0]/RD1/TXD3/SDA1_37") (pintype "bidirectional"))
    )
    (net (code "40") (name "/MZ_EN") (class "Default")
      (node (ref "U5") (pin "38") (pinfunction "P0[1]/TD1/RXD3/SCL1_38") (pintype "bidirectional"))
    )
    (net (code "41") (name "/MZ_STEP") (class "Default")
      (node (ref "U5") (pin "36") (pinfunction "P1[29]/MCOB2/PCAP1[1]/MAT0[1]_36") (pintype "bidirectional"))
    )
    (net (code "42") (name "/Mn_RST") (class "Default")
      (node (ref "U5") (pin "44") (pinfunction "P0[22]/RTS1/TD1_44") (pintype "bidirectional"))
    )
    (net (code "43") (name "/Opto_X_IN") (class "Default")
      (node (ref "U5") (pin "52") (pinfunction "P2[6]/PCAP1[0]/RI1/TRACECLK_52") (pintype "bidirectional"))
    )
    (net (code "44") (name "/Opto_Y_IN") (class "Default")
      (node (ref "U5") (pin "51") (pinfunction "P2[7]/RD2/RTS1_51") (pintype "bidirectional"))
    )
    (net (code "45") (name "/Opto_Z_IN") (class "Default")
      (node (ref "U5") (pin "50") (pinfunction "P2[8]/TD2/TXD2_50") (pintype "bidirectional"))
    )
    (net (code "47") (name "/RXD0") (class "Default")
      (node (ref "J23") (pin "4") (pinfunction "4_4") (pintype "passive"))
      (node (ref "R96") (pin "2") (pinfunction "2_2") (pintype "passive"))
      (node (ref "U5") (pin "80") (pinfunction "P0[3]/RXD0/AD0[6]_80") (pintype "bidirectional"))
    )
    (net (code "48") (name "/SD_MISO0") (class "Default")
      (node (ref "J10") (pin "7") (pinfunction "Data0_7") (pintype "passive"))
      (node (ref "U5") (pin "46") (pinfunction "P0[17]/CTS1/MISO0/MISO_46") (pintype "bidirectional"))
    )
    (net (code "49") (name "/SD_MOSI0") (class "Default")
      (node (ref "J10") (pin "3") (pinfunction "Cmd_3") (pintype "passive"))
      (node (ref "U5") (pin "45") (pinfunction "P0[18]/DCD1/MOSI0/MOSI_45") (pintype "bidirectional"))
    )
    (net (code "50") (name "/SD_SCK0") (class "Default")
      (node (ref "J10") (pin "5") (pinfunction "CLK_5") (pintype "passive"))
      (node (ref "U5") (pin "47") (pinfunction "P0[15]/TXD1/SCK0/SCK_47") (pintype "bidirectional"))
    )
    (net (code "51") (name "/SD_SSEL0") (class "Default")
      (node (ref "J10") (pin "2") (pinfunction "CardDetec/Data3_2") (pintype "passive"))
      (node (ref "U5") (pin "48") (pinfunction "P0[16]/RXD1/SSEL0/SSEL_48") (pintype "bidirectional"))
    )
    (net (code "52") (name "/TCK") (class "Default")
      (node (ref "J22") (pin "9") (pinfunction "9_9") (pintype "passive"))
      (node (ref "R83") (pin "2") (pinfunction "2_2") (pintype "passive"))
      (node (ref "U5") (pin "5") (pinfunction "TCK/SWDCLK_5") (pintype "input"))
    )
    (net (code "53") (name "/TDI") (class "Default")
      (node (ref "J22") (pin "5") (pinfunction "5_5") (pintype "passive"))
      (node (ref "R75") (pin "2") (pinfunction "2_2") (pintype "passive"))
      (node (ref "U5") (pin "2") (pinfunction "TDI_2") (pintype "input"))
    )
    (net (code "54") (name "/TDO") (class "Default")
      (node (ref "J22") (pin "13") (pinfunction "13_13") (pintype "passive"))
      (node (ref "R86") (pin "2") (pinfunction "2_2") (pintype "passive"))
      (node (ref "U5") (pin "1") (pinfunction "TDO/SWO_1") (pintype "output"))
    )
    (net (code "55") (name "/TMS") (class "Default")
      (node (ref "J22") (pin "7") (pinfunction "7_7") (pintype "passive"))
      (node (ref "R77") (pin "2") (pinfunction "2_2") (pintype "passive"))
      (node (ref "U5") (pin "3") (pinfunction "TMS/SWDIO_3") (pintype "input"))
    )
    (net (code "56") (name "/TXD0") (class "Default")
      (node (ref "J23") (pin "5") (pinfunction "5_5") (pintype "passive"))
      (node (ref "R44") (pin "2") (pinfunction "2_2") (pintype "passive"))
      (node (ref "U5") (pin "79") (pinfunction "P0[2]/TXD0/AD0[7]_79") (pintype "bidirectional"))
    )
    (net (code "57") (name "/USB_Connect") (class "Default")
      (node (ref "R76") (pin "2") (pinfunction "2_2") (pintype "passive"))
      (node (ref "U5") (pin "49") (pinfunction "P2[9]/USB_CONNECT/RXD2_49") (pintype "bidirectional"))
    )
    (net (code "58") (name "/USB_D_N") (class "Default")
      (node (ref "C42") (pin "2") (pinfunction "2_2") (pintype "passive"))
      (node (ref "J18") (pin "3") (pinfunction "3_3") (pintype "passive"))
      (node (ref "R90") (pin "2") (pinfunction "2_2") (pintype "passive"))
      (node (ref "U5") (pin "23") (pinfunction "P0[30]/USB_D_23") (pintype "bidirectional"))
    )
    (net (code "59") (name "/USB_D_P") (class "Default")
      (node (ref "C68") (pin "2") (pinfunction "2_2") (pintype "passive"))
      (node (ref "J18") (pin "4") (pinfunction "4_4") (pintype "passive"))
      (node (ref "R91") (pin "2") (pinfunction "2_2") (pintype "passive"))
      (node (ref "U5") (pin "22") (pinfunction "P0[29]/USB_D+_22") (pintype "bidirectional"))
    )
    (net (code "60") (name "/USB_PWR") (class "Default")
      (node (ref "J18") (pin "2") (pinfunction "2_2") (pintype "passive"))
      (node (ref "U5") (pin "28") (pinfunction "P1[22]/MCOB0/USB_PWRD/MAT1[0]_28") (pintype "bidirectional"))
    )
    (net (code "61") (name "/USB_Up_Led") (class "Default")
      (node (ref "R93") (pin "1") (pinfunction "1_1") (pintype "passive"))
      (node (ref "U5") (pin "25") (pinfunction "P1[18]/USB_UP_LED/PWM1[1]/CAP1[0]_25") (pintype "bidirectional"))
    )
    (net (code "62") (name "/USB_Vbus") (class "Default")
      (node (ref "C70") (pin "2") (pinfunction "2_2") (pintype "passive"))
      (node (ref "R89") (pin "2") (pinfunction "2_2") (pintype "passive"))
      (node (ref "U5") (pin "18") (pinfunction "P1[30]/VBUS/AD0[4]_18") (pintype "bidirectional"))
    )
    (net (code "63") (name "GND") (class "Default")
      (node (ref "C42") (pin "1") (pinfunction "1_1") (pintype "passive"))
      (node (ref "C43") (pin "1") (pinfunction "1_1") (pintype "passive"))
      (node (ref "C44") (pin "1") (pinfunction "1_1") (pintype "passive"))
      (node (ref "C45") (pin "2") (pinfunction "2_2") (pintype "passive"))
      (node (ref "C46") (pin "2") (pinfunction "2_2") (pintype "passive"))
      (node (ref "C47") (pin "2") (pinfunction "2_2") (pintype "passive"))
      (node (ref "C48") (pin "2") (pinfunction "2_2") (pintype "passive"))
      (node (ref "C49") (pin "2") (pinfunction "2_2") (pintype "passive"))
      (node (ref "C52") (pin "2") (pinfunction "2_2") (pintype "passive"))
      (node (ref "C55") (pin "2") (pinfunction "2_2") (pintype "passive"))
      (node (ref "C56") (pin "2") (pinfunction "2_2") (pintype "passive"))
      (node (ref "C57") (pin "2") (pinfunction "2_2") (pintype "passive"))
      (node (ref "C58") (pin "2") (pinfunction "2_2") (pintype "passive"))
      (node (ref "C59") (pin "1") (pinfunction "1_1") (pintype "passive"))
      (node (ref "C60") (pin "1") (pinfunction "1_1") (pintype "passive"))
      (node (ref "C63") (pin "2") (pinfunction "2_2") (pintype "passive"))
      (node (ref "C64") (pin "1") (pinfunction "1_1") (pintype "passive"))
      (node (ref "C65") (pin "2") (pinfunction "2_2") (pintype "passive"))
      (node (ref "C66") (pin "2") (pinfunction "2_2") (pintype "passive"))
      (node (ref "C67") (pin "1") (pinfunction "1_1") (pintype "passive"))
      (node (ref "C68") (pin "1") (pinfunction "1_1") (pintype "passive"))
      (node (ref "C70") (pin "1") (pinfunction "1_1") (pintype "passive"))
      (node (ref "D12") (pin "2") (pinfunction "A_2") (pintype "passive"))
      (node (ref "D13") (pin "1") (pinfunction "K_1") (pintype "passive"))
      (node (ref "J10") (pin "6") (pinfunction "Vss_6") (pintype "passive"))
      (node (ref "J10") (pin "9") (pinfunction "Shield_9") (pintype "passive"))
      (node (ref "J11") (pin "5") (pinfunction "SHLD_5") (pintype "passive"))
      (node (ref "J16") (pin "2") (pinfunction "2_(-)_2") (pintype "passive"))
      (node (ref "J16") (pin "3") (pinfunction "3_(-)_3") (pintype "passive"))
      (node (ref "J16") (pin "5") (pinfunction "5_(shield)_5") (pintype "passive"))
      (node (ref "J19") (pin "1") (pinfunction "1_1") (pintype "passive"))
      (node (ref "J20") (pin "14") (pinfunction "14_14") (pintype "passive"))
      (node (ref "J22") (pin "10") (pinfunction "10_10") (pintype "passive"))
      (node (ref "J22") (pin "12") (pinfunction "12_12") (pintype "passive"))
      (node (ref "J22") (pin "14") (pinfunction "14_14") (pintype "passive"))
      (node (ref "J22") (pin "16") (pinfunction "16_16") (pintype "passive"))
      (node (ref "J22") (pin "18") (pinfunction "18_18") (pintype "passive"))
      (node (ref "J22") (pin "20") (pinfunction "20_20") (pintype "passive"))
      (node (ref "J22") (pin "4") (pinfunction "4_4") (pintype "passive"))
      (node (ref "J22") (pin "6") (pinfunction "6_6") (pintype "passive"))
      (node (ref "J22") (pin "8") (pinfunction "8_8") (pintype "passive"))
      (node (ref "J23") (pin "1") (pinfunction "1_1") (pintype "passive"))
      (node (ref "L12") (pin "2") (pinfunction "2_2") (pintype "passive"))
      (node (ref "L6") (pin "1") (pinfunction "1_1") (pintype "passive"))
      (node (ref "L8") (pin "1") (pinfunction "1_1") (pintype "passive"))
      (node (ref "Q13") (pin "2") (pinfunction "S_2") (pintype "passive"))
      (node (ref "Q8") (pin "2") (pinfunction "S_2") (pintype "passive"))
      (node (ref "R100") (pin "1") (pinfunction "1_1") (pintype "passive"))
      (node (ref "R102") (pin "1") (pinfunction "1_1") (pintype "passive"))
      (node (ref "R33") (pin "1") (pinfunction "1_1") (pintype "passive"))
      (node (ref "R83") (pin "1") (pinfunction "1_1") (pintype "passive"))
      (node (ref "R95") (pin "1") (pinfunction "1_1") (pintype "passive"))
      (node (ref "S1") (pin "1") (pinfunction "1_1") (pintype "passive"))
      (node (ref "S1") (pin "2") (pinfunction "2_2") (pintype "passive"))
      (node (ref "S2") (pin "1") (pinfunction "1_1") (pintype "passive"))
      (node (ref "S2") (pin "2") (pinfunction "2_2") (pintype "passive"))
      (node (ref "U10") (pin "1") (pinfunction "GND_1") (pintype "power_in"))
      (node (ref "U5") (pin "24") (pinfunction "VSS_24") (pintype "input"))
      (node (ref "U5") (pin "33") (pinfunction "VSS_33") (pintype "input"))
      (node (ref "U5") (pin "43") (pinfunction "VSS_43") (pintype "input"))
      (node (ref "U5") (pin "57") (pinfunction "VSS_57") (pintype "input"))
      (node (ref "U5") (pin "66") (pinfunction "VSS_66") (pintype "input"))
      (node (ref "U5") (pin "78") (pinfunction "VSS_78") (pintype "input"))
      (node (ref "U6") (pin "3") (pinfunction "Inh._3") (pintype "input"))
      (node (ref "U6") (pin "7") (pinfunction "GND_7") (pintype "power_in"))
    )
    (net (code "64") (name "GND_A") (class "Default")
      (node (ref "C53") (pin "1") (pinfunction "1_1") (pintype "passive"))
      (node (ref "C54") (pin "1") (pinfunction "1_1") (pintype "passive"))
      (node (ref "L8") (pin "2") (pinfunction "2_2") (pintype "passive"))
      (node (ref "U5") (pin "9") (pinfunction "VSSA_9") (pintype "input"))
    )
    (net (code "65") (name "Net-(C61-Pad1)") (class "Default")
      (node (ref "C61") (pin "1") (pinfunction "1_1") (pintype "passive"))
      (node (ref "R95") (pin "2") (pinfunction "2_2") (pintype "passive"))
    )
    (net (code "66") (name "Net-(D10-K)") (class "Default")
      (node (ref "D10") (pin "1") (pinfunction "K_1") (pintype "passive"))
      (node (ref "R93") (pin "2") (pinfunction "2_2") (pintype "passive"))
    )
    (net (code "67") (name "Net-(D11-K)") (class "Default")
      (node (ref "C66") (pin "1") (pinfunction "1_1") (pintype "passive"))
      (node (ref "D11") (pin "1") (pinfunction "K_1") (pintype "passive"))
      (node (ref "F1") (pin "1") (pinfunction "1_1") (pintype "passive"))
    )
    (net (code "68") (name "Net-(D12-K)") (class "Default")
      (node (ref "D12") (pin "1") (pinfunction "K_1") (pintype "passive"))
      (node (ref "L13") (pin "1") (pinfunction "1_1") (pintype "passive"))
      (node (ref "U6") (pin "1") (pinfunction "Out_1") (pintype "output"))
    )
    (net (code "69") (name "Net-(D13-A)") (class "Default")
      (node (ref "D13") (pin "2") (pinfunction "A_2") (pintype "passive"))
      (node (ref "R98") (pin "1") (pinfunction "1_1") (pintype "passive"))
    )
    (net (code "70") (name "Net-(D20-A)") (class "Default")
      (node (ref "C41") (pin "1") (pinfunction "1_1") (pintype "passive"))
      (node (ref "D20") (pin "2") (pinfunction "A_2") (pintype "passive"))
      (node (ref "J24") (pin "2") (pinfunction "2_2") (pintype "passive"))
      (node (ref "Q13") (pin "3") (pinfunction "D_3") (pintype "passive"))
    )
    (net (code "71") (name "Net-(J11-D+)") (class "Default")
      (node (ref "J11") (pin "3") (pinfunction "D+_3") (pintype "input"))
      (node (ref "R87") (pin "1") (pinfunction "1_1") (pintype "passive"))
      (node (ref "R91") (pin "1") (pinfunction "1_1") (pintype "passive"))
    )
    (net (code "72") (name "Net-(J11-D-)") (class "Default")
      (node (ref "J11") (pin "2") (pinfunction "D-_2") (pintype "input"))
      (node (ref "R90") (pin "1") (pinfunction "1_1") (pintype "passive"))
    )
    (net (code "73") (name "Net-(J11-GND)") (class "Default")
      (node (ref "J11") (pin "4") (pinfunction "GND_4") (pintype "power_in"))
      (node (ref "L12") (pin "1") (pinfunction "1_1") (pintype "passive"))
    )
    (net (code "74") (name "Net-(J11-VBUS)") (class "Default")
      (node (ref "J11") (pin "1") (pinfunction "VBUS_1") (pintype "power_in"))
      (node (ref "L9") (pin "1") (pinfunction "1_1") (pintype "passive"))
    )
    (net (code "75") (name "Net-(J23-Pad6)") (class "Default")
      (node (ref "J23") (pin "6") (pinfunction "6_6") (pintype "passive"))
      (node (ref "R116") (pin "2") (pinfunction "2_2") (pintype "passive"))
    )
    (net (code "76") (name "Net-(L9-Pad2)") (class "Default")
      (node (ref "L9") (pin "2") (pinfunction "2_2") (pintype "passive"))
      (node (ref "R89") (pin "1") (pinfunction "1_1") (pintype "passive"))
    )
    (net (code "77") (name "Net-(LS1-Pad1)") (class "Default")
      (node (ref "LS1") (pin "1") (pinfunction "1_1") (pintype "passive"))
      (node (ref "R84") (pin "2") (pinfunction "2_2") (pintype "passive"))
      (node (ref "R85") (pin "1") (pinfunction "1_1") (pintype "passive"))
    )
    (net (code "78") (name "Net-(Q7-D)") (class "Default")
      (node (ref "Q7") (pin "3") (pinfunction "D_3") (pintype "passive"))
      (node (ref "R87") (pin "2") (pinfunction "2_2") (pintype "passive"))
    )
    (net (code "79") (name "Net-(Q7-G)") (class "Default")
      (node (ref "Q7") (pin "1") (pinfunction "G_1") (pintype "passive"))
      (node (ref "R15") (pin "1") (pinfunction "1_1") (pintype "passive"))
      (node (ref "R76") (pin "1") (pinfunction "1_1") (pintype "passive"))
    )
    (net (code "80") (name "Net-(Q8-D)") (class "Default")
      (node (ref "LS1") (pin "2") (pinfunction "2_2") (pintype "passive"))
      (node (ref "Q8") (pin "3") (pinfunction "D_3") (pintype "passive"))
      (node (ref "R84") (pin "1") (pinfunction "1_1") (pintype "passive"))
    )
    (net (code "81") (name "Net-(Q8-G)") (class "Default")
      (node (ref "Q8") (pin "1") (pinfunction "G_1") (pintype "passive"))
      (node (ref "R100") (pin "2") (pinfunction "2_2") (pintype "passive"))
      (node (ref "R99") (pin "2") (pinfunction "2_2") (pintype "passive"))
    )
    (net (code "82") (name "Net-(Q13-G)") (class "Default")
      (node (ref "Q13") (pin "1") (pinfunction "G_1") (pintype "passive"))
      (node (ref "R11") (pin "2") (pinfunction "2_2") (pintype "passive"))
    )
    (net (code "83") (name "Net-(U5B-RTCX1)") (class "Default")
      (node (ref "C49") (pin "1") (pinfunction "1_1") (pintype "passive"))
      (node (ref "U5") (pin "13") (pinfunction "RTCX1_13") (pintype "input"))
      (node (ref "X1") (pin "1") (pinfunction "OSC1_1") (pintype "passive"))
    )
    (net (code "84") (name "Net-(U5B-RTCX2)") (class "Default")
      (node (ref "C52") (pin "1") (pinfunction "1_1") (pintype "passive"))
      (node (ref "U5") (pin "15") (pinfunction "RTCX2_15") (pintype "output"))
      (node (ref "X1") (pin "4") (pinfunction "OSC2_4") (pintype "passive"))
    )
    (net (code "85") (name "Net-(U5B-VREFN)") (class "Default")
      (node (ref "C50") (pin "1") (pinfunction "1_1") (pintype "passive"))
      (node (ref "C51") (pin "1") (pinfunction "1_1") (pintype "passive"))
      (node (ref "L6") (pin "2") (pinfunction "2_2") (pintype "passive"))
      (node (ref "U5") (pin "12") (pinfunction "VREFN_12") (pintype "input"))
    )
    (net (code "86") (name "Net-(U5B-VREFP)") (class "Default")
      (node (ref "C50") (pin "2") (pinfunction "2_2") (pintype "passive"))
      (node (ref "C51") (pin "2") (pinfunction "2_2") (pintype "passive"))
      (node (ref "L5") (pin "2") (pinfunction "2_2") (pintype "passive"))
      (node (ref "U5") (pin "10") (pinfunction "VREFP_10") (pintype "input"))
    )
    (net (code "87") (name "Net-(U5B-XTAL1)") (class "Default")
      (node (ref "C55") (pin "1") (pinfunction "1_1") (pintype "passive"))
      (node (ref "U5") (pin "19") (pinfunction "XTAL1_19") (pintype "input"))
      (node (ref "X2") (pin "2") (pinfunction "OSC2_2") (pintype "passive"))
    )
    (net (code "88") (name "Net-(U5B-XTAL2)") (class "Default")
      (node (ref "C56") (pin "1") (pinfunction "1_1") (pintype "passive"))
      (node (ref "U5") (pin "20") (pinfunction "XTAL2_20") (pintype "output"))
      (node (ref "X2") (pin "1") (pinfunction "OSC1_1") (pintype "passive"))
    )
    (net (code "89") (name "Net-(U6-Comp)") (class "Default")
      (node (ref "C61") (pin "2") (pinfunction "2_2") (pintype "passive"))
      (node (ref "C67") (pin "2") (pinfunction "2_2") (pintype "passive"))
      (node (ref "U6") (pin "4") (pinfunction "Comp_4") (pintype "passive"))
    )
    (net (code "90") (name "Net-(U6-FB)") (class "Default")
      (node (ref "R101") (pin "1") (pinfunction "1_1") (pintype "passive"))
      (node (ref "R102") (pin "2") (pinfunction "2_2") (pintype "passive"))
      (node (ref "U6") (pin "5") (pinfunction "FB_5") (pintype "input"))
    )
    (net (code "91") (name "Net-(U6-Vcc)") (class "Default")
      (node (ref "C64") (pin "2") (pinfunction "2_2") (pintype "passive"))
      (node (ref "F1") (pin "2") (pinfunction "2_2") (pintype "passive"))
      (node (ref "U6") (pin "8") (pinfunction "Vcc_8") (pintype "power_in"))
    )
    (net (code "92") (name "V3.3") (class "Default")
      (node (ref "C43") (pin "2") (pinfunction "2_2") (pintype "passive"))
      (node (ref "C44") (pin "2") (pinfunction "2_2") (pintype "passive"))
      (node (ref "C45") (pin "1") (pinfunction "1_1") (pintype "passive"))
      (node (ref "C46") (pin "1") (pinfunction "1_1") (pintype "passive"))
      (node (ref "C47") (pin "1") (pinfunction "1_1") (pintype "passive"))
      (node (ref "C48") (pin "1") (pinfunction "1_1") (pintype "passive"))
      (node (ref "C57") (pin "1") (pinfunction "1_1") (pintype "passive"))
      (node (ref "C58") (pin "1") (pinfunction "1_1") (pintype "passive"))
      (node (ref "D10") (pin "2") (pinfunction "A_2") (pintype "passive"))
      (node (ref "D19") (pin "2") (pinfunction "A_2") (pintype "passive"))
      (node (ref "J10") (pin "4") (pinfunction "Vdd_4") (pintype "passive"))
      (node (ref "J20") (pin "2") (pinfunction "2_2") (pintype "passive"))
      (node (ref "J22") (pin "1") (pinfunction "1_1") (pintype "passive"))
      (node (ref "J22") (pin "2") (pinfunction "2_2") (pintype "passive"))
      (node (ref "L5") (pin "1") (pinfunction "1_1") (pintype "passive"))
      (node (ref "L7") (pin "1") (pinfunction "1_1") (pintype "passive"))
      (node (ref "Q7") (pin "2") (pinfunction "S_2") (pintype "passive"))
      (node (ref "R103") (pin "2") (pinfunction "2_2") (pintype "passive"))
      (node (ref "R115") (pin "1") (pinfunction "1_1") (pintype "passive"))
      (node (ref "R15") (pin "2") (pinfunction "2_2") (pintype "passive"))
      (node (ref "R72") (pin "1") (pinfunction "1_1") (pintype "passive"))
      (node (ref "R74") (pin "2") (pinfunction "2_2") (pintype "passive"))
      (node (ref "R75") (pin "1") (pinfunction "1_1") (pintype "passive"))
      (node (ref "R77") (pin "1") (pinfunction "1_1") (pintype "passive"))
      (node (ref "R85") (pin "2") (pinfunction "2_2") (pintype "passive"))
      (node (ref "R86") (pin "1") (pinfunction "1_1") (pintype "passive"))
      (node (ref "R98") (pin "2") (pinfunction "2_2") (pintype "passive"))
      (node (ref "U10") (pin "2") (pinfunction "OUT_2") (pintype "power_in"))
      (node (ref "U5") (pin "16") (pinfunction "VBAT_16") (pintype "input"))
      (node (ref "U5") (pin "21") (pinfunction "VDD(3V3)_21") (pintype "input"))
      (node (ref "U5") (pin "34") (pinfunction "VDD(REG)(3V3)_34") (pintype "input"))
      (node (ref "U5") (pin "42") (pinfunction "VDD(3V3)_42") (pintype "input"))
      (node (ref "U5") (pin "56") (pinfunction "VDD(3V3)_56") (pintype "input"))
      (node (ref "U5") (pin "67") (pinfunction "VDD(REG)(3V3)_67") (pintype "input"))
      (node (ref "U5") (pin "77") (pinfunction "VDD(3V3)_77") (pintype "input"))
    )
    (net (code "93") (name "V5") (class "Default")
      (node (ref "C63") (pin "1") (pinfunction "1_1") (pintype "passive"))
      (node (ref "D19") (pin "1") (pinfunction "K_1") (pintype "passive"))
      (node (ref "J18") (pin "15") (pinfunction "15_15") (pintype "passive"))
      (node (ref "L13") (pin "2") (pinfunction "2_2") (pintype "passive"))
      (node (ref "R101") (pin "2") (pinfunction "2_2") (pintype "passive"))
      (node (ref "U10") (pin "3") (pinfunction "IN_3") (pintype "power_in"))
    )
    (net (code "94") (name "VA3.3") (class "Default")
      (node (ref "C53") (pin "2") (pinfunction "2_2") (pintype "passive"))
      (node (ref "C54") (pin "2") (pinfunction "2_2") (pintype "passive"))
      (node (ref "L7") (pin "2") (pinfunction "2_2") (pintype "passive"))
      (node (ref "U5") (pin "8") (pinfunction "VDDA_8") (pintype "input"))
    )
    (net (code "95") (name "VMM") (class "Default")
      (node (ref "C41") (pin "2") (pinfunction "2_2") (pintype "passive"))
      (node (ref "C65") (pin "1") (pinfunction "1_1") (pintype "passive"))
      (node (ref "D11") (pin "2") (pinfunction "A_2") (pintype "passive"))
      (node (ref "D20") (pin "1") (pinfunction "K_1") (pintype "passive"))
      (node (ref "J16") (pin "1") (pinfunction "1_(+)_1") (pintype "passive"))
      (node (ref "J16") (pin "4") (pinfunction "4_(+)_4") (pintype "passive"))
      (node (ref "J20") (pin "1") (pinfunction "1_1") (pintype "passive"))
      (node (ref "J24") (pin "1") (pinfunction "1_1") (pintype "passive"))
    )
    (net (code "96") (name "unconnected-(J10-Data1-Pad8)") (class "Default")
      (node (ref "J10") (pin "8") (pinfunction "Data1_8") (pintype "passive+no_connect"))
    )
    (net (code "97") (name "unconnected-(J10-Data2-Pad1)") (class "Default")
      (node (ref "J10") (pin "1") (pinfunction "Data2_1") (pintype "passive+no_connect"))
    )
    (net (code "98") (name "unconnected-(J10-Shield-Pad10)") (class "Default")
      (node (ref "J10") (pin "10") (pinfunction "Shield_10") (pintype "passive+no_connect"))
    )
    (net (code "99") (name "unconnected-(J19-Pad2)") (class "Default")
      (node (ref "J19") (pin "2") (pinfunction "2_2") (pintype "passive+no_connect"))
    )
    (net (code "100") (name "unconnected-(J19-Pad3)") (class "Default")
      (node (ref "J19") (pin "3") (pinfunction "3_3") (pintype "passive+no_connect"))
    )
    (net (code "101") (name "unconnected-(J19-Pad6)") (class "Default")
      (node (ref "J19") (pin "6") (pinfunction "6_6") (pintype "passive+no_connect"))
    )
    (net (code "102") (name "unconnected-(J20-Pad15)") (class "Default")
      (node (ref "J20") (pin "15") (pinfunction "15_15") (pintype "passive+no_connect"))
    )
    (net (code "103") (name "unconnected-(J22-Pad11)") (class "Default")
      (node (ref "J22") (pin "11") (pinfunction "11_11") (pintype "passive"))
    )
    (net (code "104") (name "unconnected-(J22-Pad17)") (class "Default")
      (node (ref "J22") (pin "17") (pinfunction "17_17") (pintype "passive+no_connect"))
    )
    (net (code "105") (name "unconnected-(J22-Pad19)") (class "Default")
      (node (ref "J22") (pin "19") (pinfunction "19_19") (pintype "passive+no_connect"))
    )
    (net (code "106") (name "unconnected-(J23-Pad2)") (class "Default")
      (node (ref "J23") (pin "2") (pinfunction "2_2") (pintype "passive+no_connect"))
    )
    (net (code "107") (name "unconnected-(J23-Pad3)") (class "Default")
      (node (ref "J23") (pin "3") (pinfunction "3_3") (pintype "passive+no_connect"))
    )
    (net (code "108") (name "unconnected-(U5B-*RSTOUT-Pad11)") (class "Default")
      (node (ref "U5") (pin "11") (pinfunction "*RSTOUT_11") (pintype "output+no_connect"))
    )
    (net (code "109") (name "unconnected-(U6-Sync-Pad2)") (class "Default")
      (node (ref "U6") (pin "2") (pinfunction "Sync_2") (pintype "bidirectional+no_connect"))
    )
    (net (code "110") (name "unconnected-(U6-Vref-Pad6)") (class "Default")
      (node (ref "U6") (pin "6") (pinfunction "Vref_6") (pintype "output+no_connect"))
    )
  )
)
